# sharp.net
KiCad netlist of a schematic drawn in Altium Designer
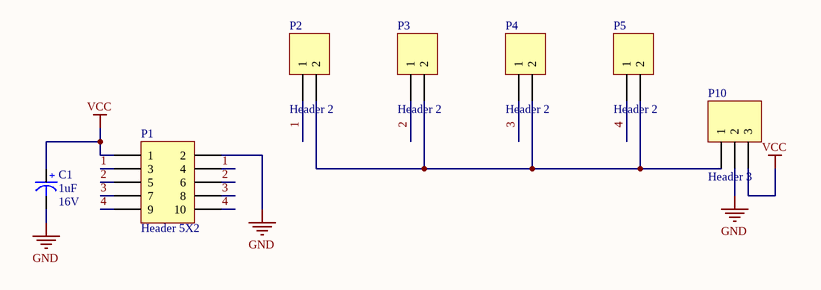
[diagram p0: sharp.SchDoc]

(export (version "E")
  (design (tool "Eeschema 10.0.6"))
  (components
    (comp (ref "C1")
      (value "1uF")
      (footprint "cap 01")
      (description "Polar Capacitor")
      (fields (field (name "VOLTAGE") "16V") (field (name "DESIGNER") "Saeid Jorablo"))
      (libsource (lib "My_Library") (part "Cap-Polar"))
    )
    (comp (ref "P1")
      (value "Header 5X2")
      (footprint "HDR2X5")
      (description "Header, 5-Pin, Dual row")
      (fields (field (name "PUBLISHER") "Altium Limited"))
      (libsource (lib "Miscellaneous Connectors") (part "Header 5X2"))
    )
    (comp (ref "P2")
      (value "Header 2")
      (footprint "HDR1X2")
      (description "Header, 2-Pin")
      (fields (field (name "PUBLISHER") "Altium Limited"))
      (libsource (lib "Miscellaneous Connectors") (part "Header 2"))
    )
    (comp (ref "P3")
      (value "Header 2")
      (footprint "HDR1X2")
      (description "Header, 2-Pin")
      (fields (field (name "PUBLISHER") "Altium Limited"))
      (libsource (lib "Miscellaneous Connectors") (part "Header 2"))
    )
    (comp (ref "P4")
      (value "Header 2")
      (footprint "HDR1X2")
      (description "Header, 2-Pin")
      (fields (field (name "PUBLISHER") "Altium Limited"))
      (libsource (lib "Miscellaneous Connectors") (part "Header 2"))
    )
    (comp (ref "P5")
      (value "Header 2")
      (footprint "HDR1X2")
      (description "Header, 2-Pin")
      (fields (field (name "PUBLISHER") "Altium Limited"))
      (libsource (lib "Miscellaneous Connectors") (part "Header 2"))
    )
    (comp (ref "P10")
      (value "Header 3")
      (footprint "HDR1X3")
      (description "Header, 3-Pin")
      (fields (field (name "PUBLISHER") "Altium Limited"))
      (libsource (lib "Miscellaneous Connectors") (part "Header 3"))
    )
  )
  (nets
    (net (code "1") (name "/1") (class "Default")
      (node (ref "P1") (pin "3") (pinfunction "3_3") (pintype "passive"))
      (node (ref "P1") (pin "4") (pinfunction "4_4") (pintype "passive"))
      (node (ref "P2") (pin "1") (pinfunction "1_1") (pintype "passive"))
    )
    (net (code "2") (name "/2") (class "Default")
      (node (ref "P1") (pin "5") (pinfunction "5_5") (pintype "passive"))
      (node (ref "P1") (pin "6") (pinfunction "6_6") (pintype "passive"))
      (node (ref "P3") (pin "1") (pinfunction "1_1") (pintype "passive"))
    )
    (net (code "3") (name "/3") (class "Default")
      (node (ref "P1") (pin "7") (pinfunction "7_7") (pintype "passive"))
      (node (ref "P1") (pin "8") (pinfunction "8_8") (pintype "passive"))
      (node (ref "P4") (pin "1") (pinfunction "1_1") (pintype "passive"))
    )
    (net (code "4") (name "/4") (class "Default")
      (node (ref "P1") (pin "10") (pinfunction "10_10") (pintype "passive"))
      (node (ref "P1") (pin "9") (pinfunction "9_9") (pintype "passive"))
      (node (ref "P5") (pin "1") (pinfunction "1_1") (pintype "passive"))
    )
    (net (code "5") (name "GND") (class "Default")
      (node (ref "C1") (pin "2") (pinfunction "-_2") (pintype "passive"))
      (node (ref "P1") (pin "2") (pinfunction "2_2") (pintype "passive"))
      (node (ref "P10") (pin "2") (pinfunction "2_2") (pintype "passive"))
    )
    (net (code "6") (name "Net-(P10-Pad1)") (class "Default")
      (node (ref "P10") (pin "1") (pinfunction "1_1") (pintype "passive"))
      (node (ref "P2") (pin "2") (pinfunction "2_2") (pintype "passive"))
      (node (ref "P3") (pin "2") (pinfunction "2_2") (pintype "passive"))
      (node (ref "P4") (pin "2") (pinfunction "2_2") (pintype "passive"))
      (node (ref "P5") (pin "2") (pinfunction "2_2") (pintype "passive"))
    )
    (net (code "7") (name "VCC") (class "Default")
      (node (ref "C1") (pin "1") (pinfunction "+_1") (pintype "passive"))
      (node (ref "P1") (pin "1") (pinfunction "1_1") (pintype "passive"))
      (node (ref "P10") (pin "3") (pinfunction "3_3") (pintype "passive"))
    )
  )
)
